# MRCS-Approach-Indicator.net
KiCad netlist of a schematic drawn in EAGLE
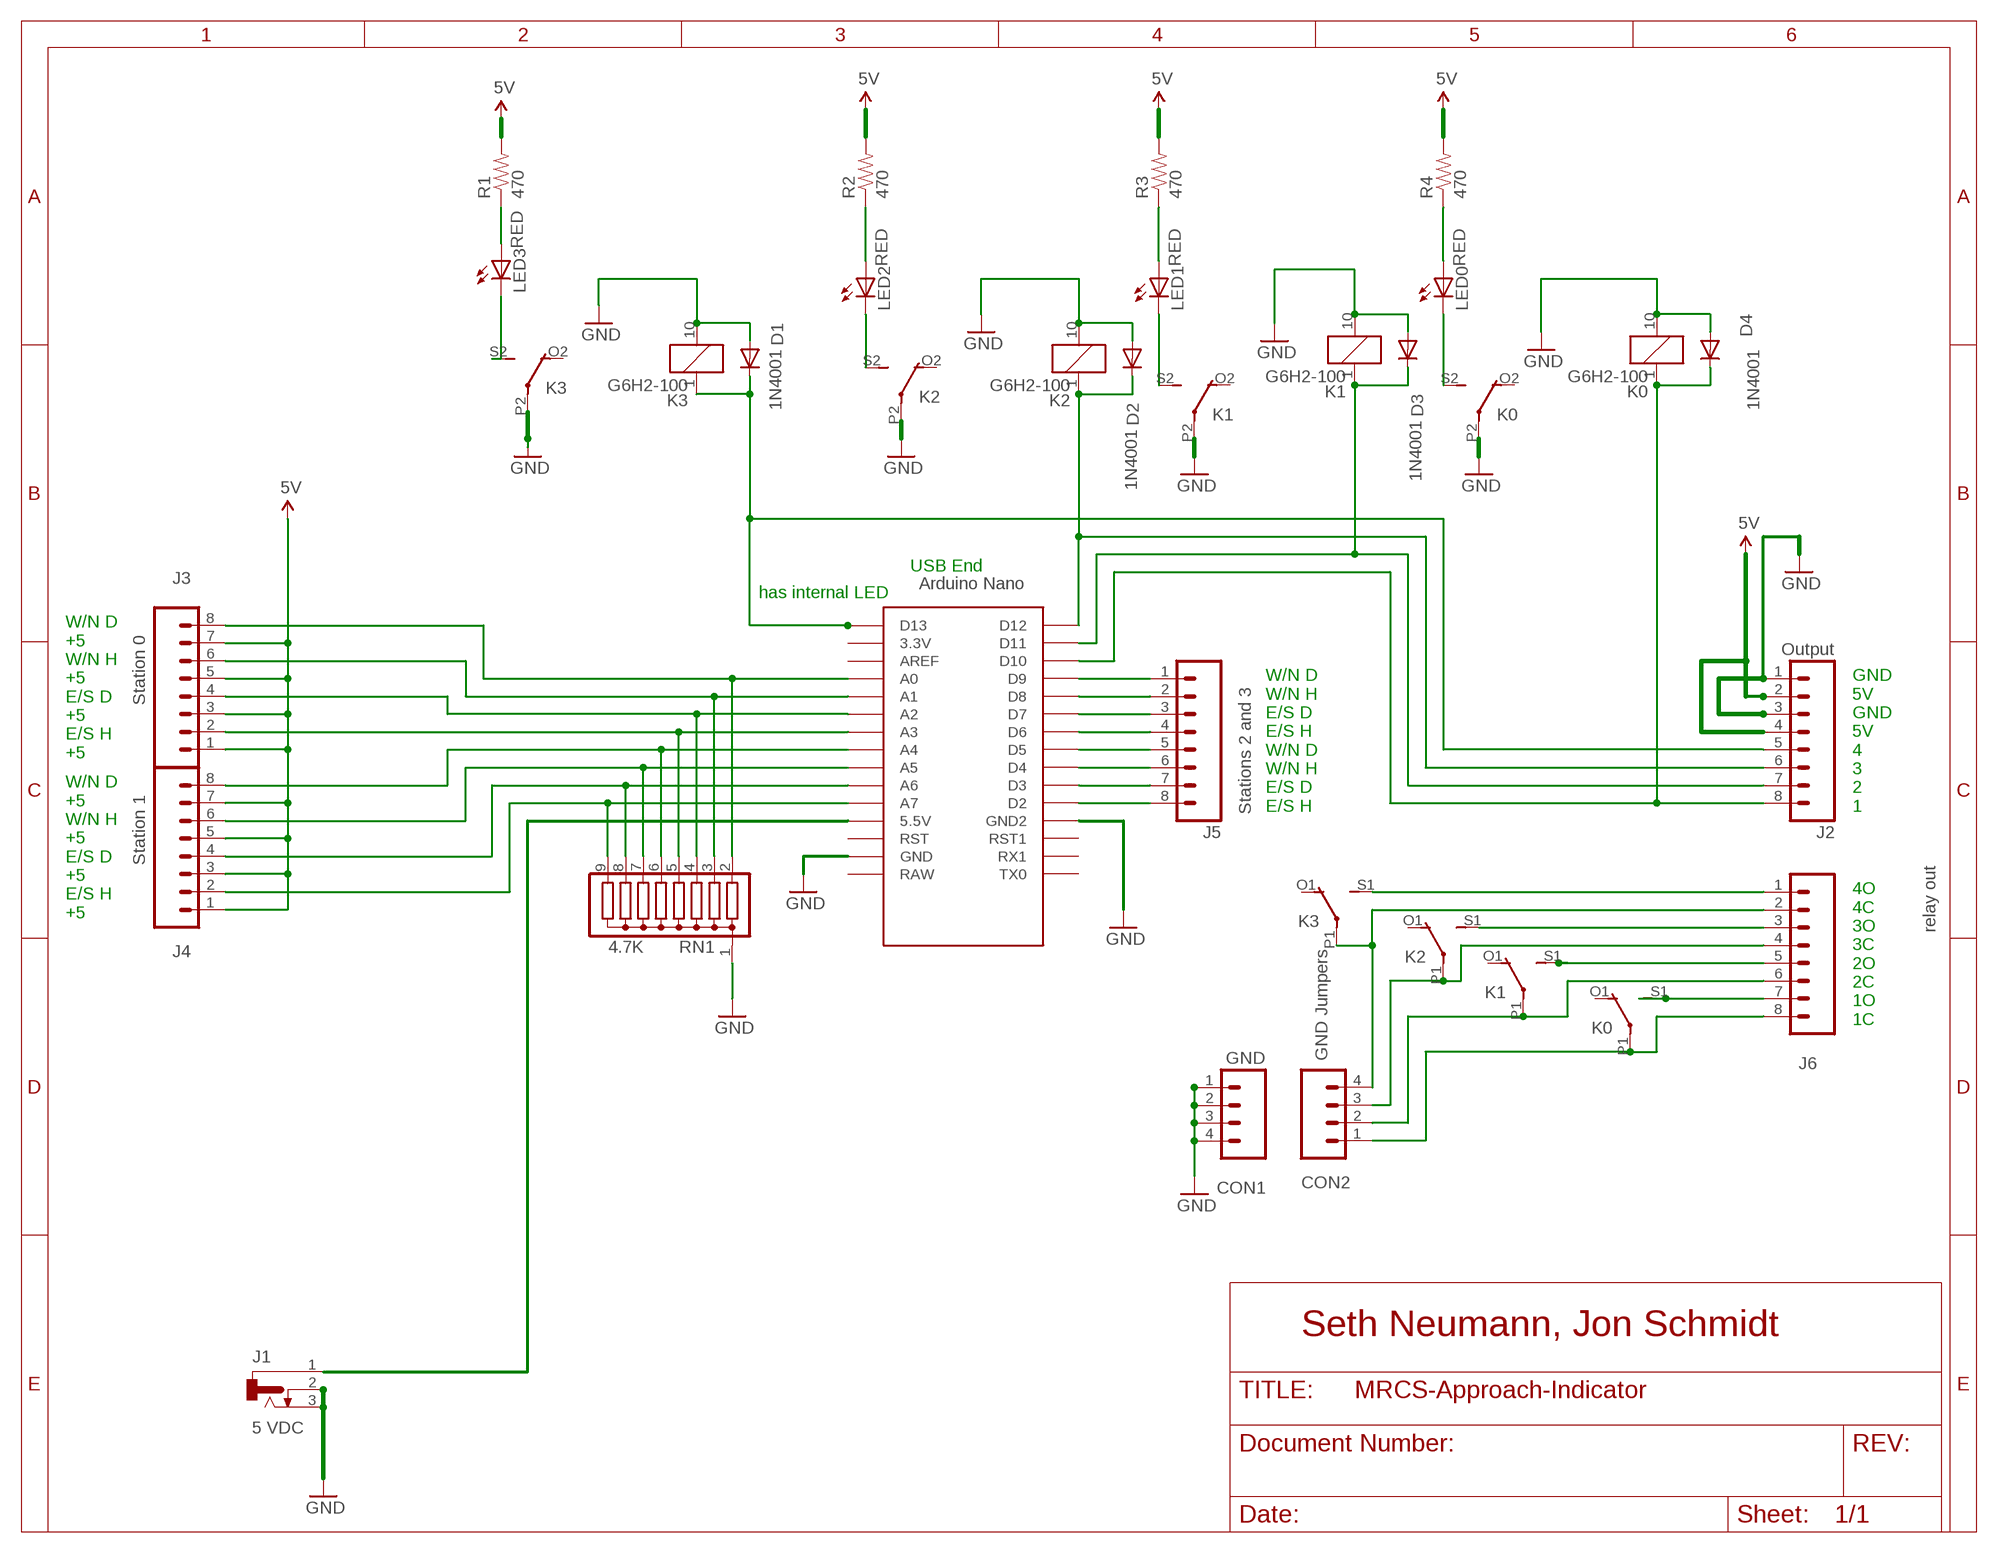
[diagram p0: schematic, sheet 1]

(export (version "E")
  (design (tool "Eeschema 10.0.6"))
  (components
    (comp (ref "CON1")
      (value "GND")
      (footprint "eagle-import:1X04_LOCK")
      (libsource (lib "eagle-import") (part "CONNECTOR-M04LOCK"))
    )
    (comp (ref "CON2")
      (value "GND Jumpers")
      (footprint "eagle-import:1X04_LOCK")
      (libsource (lib "eagle-import") (part "CONNECTOR-M04LOCK"))
    )
    (comp (ref "D1")
      (value "1N4001")
      (footprint "eagle-import:DIODE-1N4001")
      (libsource (lib "eagle-import") (part "DIODEPTH"))
    )
    (comp (ref "D2")
      (value "1N4001")
      (footprint "eagle-import:DIODE-1N4001")
      (libsource (lib "eagle-import") (part "DIODEPTH"))
    )
    (comp (ref "D3")
      (value "1N4001")
      (footprint "eagle-import:DIODE-1N4001")
      (libsource (lib "eagle-import") (part "DIODEPTH"))
    )
    (comp (ref "D4")
      (value "1N4001")
      (footprint "eagle-import:DIODE-1N4001")
      (libsource (lib "eagle-import") (part "DIODEPTH"))
    )
    (comp (ref "J1")
      (value "5 VDC")
      (footprint "eagle-import:DCJ0202")
      (libsource (lib "eagle-import") (part "CONNECTOR-DC-POWER-RA"))
    )
    (comp (ref "J2")
      (value "Output")
      (footprint "eagle-import:1X08_LOCK")
      (libsource (lib "eagle-import") (part "CONNECTOR-M08LOCK"))
    )
    (comp (ref "J3")
      (value "Station 0")
      (footprint "eagle-import:1X08_LOCK")
      (libsource (lib "eagle-import") (part "CONNECTOR-M08LOCK"))
    )
    (comp (ref "J4")
      (value "Station 1")
      (footprint "eagle-import:1X08_LOCK")
      (libsource (lib "eagle-import") (part "CONNECTOR-M08LOCK"))
    )
    (comp (ref "J5")
      (value "Stations 2 and 3")
      (footprint "eagle-import:1X08_LOCK")
      (libsource (lib "eagle-import") (part "CONNECTOR-M08LOCK"))
    )
    (comp (ref "J6")
      (value "relay out")
      (footprint "eagle-import:1X08_LOCK")
      (libsource (lib "eagle-import") (part "CONNECTOR-M08LOCK"))
    )
    (comp (ref "K0")
      (value "G6H2-100")
      (footprint "eagle-import:G6H2-100")
      (libsource (lib "eagle-import") (part "G6H2-100"))
    )
    (comp (ref "K1")
      (value "G6H2-100")
      (footprint "eagle-import:G6H2-100")
      (libsource (lib "eagle-import") (part "G6H2-100"))
    )
    (comp (ref "K2")
      (value "G6H2-100")
      (footprint "eagle-import:G6H2-100")
      (libsource (lib "eagle-import") (part "G6H2-100"))
    )
    (comp (ref "K3")
      (value "G6H2-100")
      (footprint "eagle-import:G6H2-100")
      (libsource (lib "eagle-import") (part "G6H2-100"))
    )
    (comp (ref "LED0")
      (value "RED")
      (footprint "eagle-import:LED3MM")
      (libsource (lib "eagle-import") (part "LEDLED3MM"))
    )
    (comp (ref "LED1")
      (value "RED")
      (footprint "eagle-import:LED3MM")
      (libsource (lib "eagle-import") (part "LEDLED3MM"))
    )
    (comp (ref "LED2")
      (value "RED")
      (footprint "eagle-import:LED3MM")
      (libsource (lib "eagle-import") (part "LEDLED3MM"))
    )
    (comp (ref "LED3")
      (value "RED")
      (footprint "eagle-import:LED3MM")
      (libsource (lib "eagle-import") (part "LEDLED3MM"))
    )
    (comp (ref "NANO")
      (value "NANO")
      (footprint "eagle-import:NANO")
      (libsource (lib "eagle-import") (part "NANO"))
    )
    (comp (ref "R1")
      (value "470")
      (footprint "eagle-import:AXIAL-0.4-RES")
      (libsource (lib "eagle-import") (part "RPTH04"))
    )
    (comp (ref "R2")
      (value "470")
      (footprint "eagle-import:AXIAL-0.4-RES")
      (libsource (lib "eagle-import") (part "RPTH04"))
    )
    (comp (ref "R3")
      (value "470")
      (footprint "eagle-import:AXIAL-0.4-RES")
      (libsource (lib "eagle-import") (part "RPTH04"))
    )
    (comp (ref "R4")
      (value "470")
      (footprint "eagle-import:AXIAL-0.4-RES")
      (libsource (lib "eagle-import") (part "RPTH04"))
    )
    (comp (ref "RN1")
      (value "4.7K")
      (footprint "eagle-import:SIL9")
      (libsource (lib "eagle-import") (part "G08R"))
    )
  )
  (nets
    (net (code "1") (name "5V") (class "Default")
      (node (ref "J1") (pin "1") (pinfunction "1_1") (pintype "passive"))
      (node (ref "J2") (pin "2") (pinfunction "2_2") (pintype "passive"))
      (node (ref "J2") (pin "4") (pinfunction "4_4") (pintype "passive"))
      (node (ref "J3") (pin "1") (pinfunction "1_1") (pintype "passive"))
      (node (ref "J3") (pin "3") (pinfunction "3_3") (pintype "passive"))
      (node (ref "J3") (pin "5") (pinfunction "5_5") (pintype "passive"))
      (node (ref "J3") (pin "7") (pinfunction "7_7") (pintype "passive"))
      (node (ref "J4") (pin "1") (pinfunction "1_1") (pintype "passive"))
      (node (ref "J4") (pin "3") (pinfunction "3_3") (pintype "passive"))
      (node (ref "J4") (pin "5") (pinfunction "5_5") (pintype "passive"))
      (node (ref "J4") (pin "7") (pinfunction "7_7") (pintype "passive"))
      (node (ref "NANO") (pin "5V") (pinfunction "5.5V_5V") (pintype "bidirectional"))
      (node (ref "R1") (pin "P$2") (pinfunction "2_P$2") (pintype "passive"))
      (node (ref "R2") (pin "P$2") (pinfunction "2_P$2") (pintype "passive"))
      (node (ref "R3") (pin "P$2") (pinfunction "2_P$2") (pintype "passive"))
      (node (ref "R4") (pin "P$2") (pinfunction "2_P$2") (pintype "passive"))
    )
    (net (code "2") (name "GND") (class "Default")
      (node (ref "CON1") (pin "1") (pinfunction "1_1") (pintype "passive"))
      (node (ref "CON1") (pin "2") (pinfunction "2_2") (pintype "passive"))
      (node (ref "CON1") (pin "3") (pinfunction "3_3") (pintype "passive"))
      (node (ref "CON1") (pin "4") (pinfunction "4_4") (pintype "passive"))
      (node (ref "D1") (pin "A") (pinfunction "A_A") (pintype "passive"))
      (node (ref "D2") (pin "A") (pinfunction "A_A") (pintype "passive"))
      (node (ref "D3") (pin "A") (pinfunction "A_A") (pintype "passive"))
      (node (ref "D4") (pin "A") (pinfunction "A_A") (pintype "passive"))
      (node (ref "J1") (pin "2") (pinfunction "2_2") (pintype "passive"))
      (node (ref "J1") (pin "3") (pinfunction "3_3") (pintype "passive"))
      (node (ref "J2") (pin "1") (pinfunction "1_1") (pintype "passive"))
      (node (ref "J2") (pin "3") (pinfunction "3_3") (pintype "passive"))
      (node (ref "K0") (pin "10") (pinfunction "2_10") (pintype "passive"))
      (node (ref "K0") (pin "P2") (pinfunction "P_P2") (pintype "passive"))
      (node (ref "K1") (pin "10") (pinfunction "2_10") (pintype "passive"))
      (node (ref "K1") (pin "P2") (pinfunction "P_P2") (pintype "passive"))
      (node (ref "K2") (pin "10") (pinfunction "2_10") (pintype "passive"))
      (node (ref "K2") (pin "P2") (pinfunction "P_P2") (pintype "passive"))
      (node (ref "K3") (pin "10") (pinfunction "2_10") (pintype "passive"))
      (node (ref "K3") (pin "P2") (pinfunction "P_P2") (pintype "passive"))
      (node (ref "NANO") (pin "GND") (pinfunction "GND_GND") (pintype "bidirectional"))
      (node (ref "NANO") (pin "GND1") (pinfunction "GND2_GND1") (pintype "bidirectional"))
      (node (ref "RN1") (pin "1") (pinfunction "1_1") (pintype "passive"))
    )
    (net (code "3") (name "Net-(D1-PadC)") (class "Default")
      (node (ref "D1") (pin "C") (pinfunction "C_C") (pintype "passive"))
      (node (ref "J2") (pin "5") (pinfunction "5_5") (pintype "passive"))
      (node (ref "K3") (pin "1") (pinfunction "1_1") (pintype "passive"))
      (node (ref "NANO") (pin "D13") (pinfunction "D13_D13") (pintype "bidirectional"))
    )
    (net (code "4") (name "Net-(D2-PadC)") (class "Default")
      (node (ref "D2") (pin "C") (pinfunction "C_C") (pintype "passive"))
      (node (ref "J2") (pin "6") (pinfunction "6_6") (pintype "passive"))
      (node (ref "K2") (pin "1") (pinfunction "1_1") (pintype "passive"))
      (node (ref "NANO") (pin "D12") (pinfunction "D12_D12") (pintype "bidirectional"))
    )
    (net (code "5") (name "Net-(D3-PadC)") (class "Default")
      (node (ref "D3") (pin "C") (pinfunction "C_C") (pintype "passive"))
      (node (ref "J2") (pin "7") (pinfunction "7_7") (pintype "passive"))
      (node (ref "K1") (pin "1") (pinfunction "1_1") (pintype "passive"))
      (node (ref "NANO") (pin "D11") (pinfunction "D11_D11") (pintype "bidirectional"))
    )
    (net (code "6") (name "Net-(D4-PadC)") (class "Default")
      (node (ref "D4") (pin "C") (pinfunction "C_C") (pintype "passive"))
      (node (ref "J2") (pin "8") (pinfunction "8_8") (pintype "passive"))
      (node (ref "K0") (pin "1") (pinfunction "1_1") (pintype "passive"))
      (node (ref "NANO") (pin "D10") (pinfunction "D10_D10") (pintype "bidirectional"))
    )
    (net (code "7") (name "Net-(J3-Pad2)") (class "Default")
      (node (ref "J3") (pin "2") (pinfunction "2_2") (pintype "passive"))
      (node (ref "NANO") (pin "A3") (pinfunction "A3_A3") (pintype "bidirectional"))
      (node (ref "RN1") (pin "5") (pinfunction "5_5") (pintype "passive"))
    )
    (net (code "8") (name "Net-(J3-Pad4)") (class "Default")
      (node (ref "J3") (pin "4") (pinfunction "4_4") (pintype "passive"))
      (node (ref "NANO") (pin "A2") (pinfunction "A2_A2") (pintype "bidirectional"))
      (node (ref "RN1") (pin "4") (pinfunction "4_4") (pintype "passive"))
    )
    (net (code "9") (name "Net-(J3-Pad6)") (class "Default")
      (node (ref "J3") (pin "6") (pinfunction "6_6") (pintype "passive"))
      (node (ref "NANO") (pin "A1") (pinfunction "A1_A1") (pintype "bidirectional"))
      (node (ref "RN1") (pin "3") (pinfunction "3_3") (pintype "passive"))
    )
    (net (code "10") (name "Net-(J3-Pad8)") (class "Default")
      (node (ref "J3") (pin "8") (pinfunction "8_8") (pintype "passive"))
      (node (ref "NANO") (pin "A0") (pinfunction "A0_A0") (pintype "bidirectional"))
      (node (ref "RN1") (pin "2") (pinfunction "2_2") (pintype "passive"))
    )
    (net (code "11") (name "Net-(J4-Pad2)") (class "Default")
      (node (ref "J4") (pin "2") (pinfunction "2_2") (pintype "passive"))
      (node (ref "NANO") (pin "A7") (pinfunction "A7_A7") (pintype "bidirectional"))
      (node (ref "RN1") (pin "9") (pinfunction "9_9") (pintype "passive"))
    )
    (net (code "12") (name "Net-(J4-Pad4)") (class "Default")
      (node (ref "J4") (pin "4") (pinfunction "4_4") (pintype "passive"))
      (node (ref "NANO") (pin "A6") (pinfunction "A6_A6") (pintype "bidirectional"))
      (node (ref "RN1") (pin "8") (pinfunction "8_8") (pintype "passive"))
    )
    (net (code "13") (name "Net-(J4-Pad6)") (class "Default")
      (node (ref "J4") (pin "6") (pinfunction "6_6") (pintype "passive"))
      (node (ref "NANO") (pin "A5") (pinfunction "A5_A5") (pintype "bidirectional"))
      (node (ref "RN1") (pin "7") (pinfunction "7_7") (pintype "passive"))
    )
    (net (code "14") (name "Net-(J4-Pad8)") (class "Default")
      (node (ref "J4") (pin "8") (pinfunction "8_8") (pintype "passive"))
      (node (ref "NANO") (pin "A4") (pinfunction "A4_A4") (pintype "bidirectional"))
      (node (ref "RN1") (pin "6") (pinfunction "6_6") (pintype "passive"))
    )
    (net (code "15") (name "Net-(J5-Pad1)") (class "Default")
      (node (ref "J5") (pin "1") (pinfunction "1_1") (pintype "passive"))
      (node (ref "NANO") (pin "D9") (pinfunction "D9_D9") (pintype "bidirectional"))
    )
    (net (code "16") (name "Net-(J5-Pad2)") (class "Default")
      (node (ref "J5") (pin "2") (pinfunction "2_2") (pintype "passive"))
      (node (ref "NANO") (pin "D8") (pinfunction "D8_D8") (pintype "bidirectional"))
    )
    (net (code "17") (name "Net-(J5-Pad3)") (class "Default")
      (node (ref "J5") (pin "3") (pinfunction "3_3") (pintype "passive"))
      (node (ref "NANO") (pin "D7") (pinfunction "D7_D7") (pintype "bidirectional"))
    )
    (net (code "18") (name "Net-(J5-Pad4)") (class "Default")
      (node (ref "J5") (pin "4") (pinfunction "4_4") (pintype "passive"))
      (node (ref "NANO") (pin "D6") (pinfunction "D6_D6") (pintype "bidirectional"))
    )
    (net (code "19") (name "Net-(J5-Pad5)") (class "Default")
      (node (ref "J5") (pin "5") (pinfunction "5_5") (pintype "passive"))
      (node (ref "NANO") (pin "D5") (pinfunction "D5_D5") (pintype "bidirectional"))
    )
    (net (code "20") (name "Net-(J5-Pad6)") (class "Default")
      (node (ref "J5") (pin "6") (pinfunction "6_6") (pintype "passive"))
      (node (ref "NANO") (pin "D4") (pinfunction "D4_D4") (pintype "bidirectional"))
    )
    (net (code "21") (name "Net-(J5-Pad7)") (class "Default")
      (node (ref "J5") (pin "7") (pinfunction "7_7") (pintype "passive"))
      (node (ref "NANO") (pin "D3") (pinfunction "D3_D3") (pintype "bidirectional"))
    )
    (net (code "22") (name "Net-(J5-Pad8)") (class "Default")
      (node (ref "J5") (pin "8") (pinfunction "8_8") (pintype "passive"))
      (node (ref "NANO") (pin "D2") (pinfunction "D2_D2") (pintype "bidirectional"))
    )
    (net (code "23") (name "Net-(K0B-P)") (class "Default")
      (node (ref "CON2") (pin "1") (pinfunction "1_1") (pintype "passive"))
      (node (ref "J6") (pin "8") (pinfunction "8_8") (pintype "passive"))
      (node (ref "K0") (pin "P1") (pinfunction "P_P1") (pintype "passive"))
    )
    (net (code "24") (name "Net-(K0B-S)") (class "Default")
      (node (ref "J6") (pin "7") (pinfunction "7_7") (pintype "passive"))
      (node (ref "K0") (pin "S1") (pinfunction "S_S1") (pintype "passive"))
    )
    (net (code "25") (name "Net-(K0C-S)") (class "Default")
      (node (ref "K0") (pin "S2") (pinfunction "S_S2") (pintype "passive"))
      (node (ref "LED0") (pin "K") (pinfunction "C_K") (pintype "passive"))
    )
    (net (code "26") (name "Net-(K1B-P)") (class "Default")
      (node (ref "CON2") (pin "2") (pinfunction "2_2") (pintype "passive"))
      (node (ref "J6") (pin "6") (pinfunction "6_6") (pintype "passive"))
      (node (ref "K1") (pin "P1") (pinfunction "P_P1") (pintype "passive"))
    )
    (net (code "27") (name "Net-(K1B-S)") (class "Default")
      (node (ref "J6") (pin "5") (pinfunction "5_5") (pintype "passive"))
      (node (ref "K1") (pin "S1") (pinfunction "S_S1") (pintype "passive"))
    )
    (net (code "28") (name "Net-(K1C-S)") (class "Default")
      (node (ref "K1") (pin "S2") (pinfunction "S_S2") (pintype "passive"))
      (node (ref "LED1") (pin "K") (pinfunction "C_K") (pintype "passive"))
    )
    (net (code "29") (name "Net-(K2B-P)") (class "Default")
      (node (ref "CON2") (pin "3") (pinfunction "3_3") (pintype "passive"))
      (node (ref "J6") (pin "4") (pinfunction "4_4") (pintype "passive"))
      (node (ref "K2") (pin "P1") (pinfunction "P_P1") (pintype "passive"))
    )
    (net (code "30") (name "Net-(K2B-S)") (class "Default")
      (node (ref "J6") (pin "3") (pinfunction "3_3") (pintype "passive"))
      (node (ref "K2") (pin "S1") (pinfunction "S_S1") (pintype "passive"))
    )
    (net (code "31") (name "Net-(K2C-S)") (class "Default")
      (node (ref "K2") (pin "S2") (pinfunction "S_S2") (pintype "passive"))
      (node (ref "LED2") (pin "K") (pinfunction "C_K") (pintype "passive"))
    )
    (net (code "32") (name "Net-(K3B-P)") (class "Default")
      (node (ref "CON2") (pin "4") (pinfunction "4_4") (pintype "passive"))
      (node (ref "J6") (pin "2") (pinfunction "2_2") (pintype "passive"))
      (node (ref "K3") (pin "P1") (pinfunction "P_P1") (pintype "passive"))
    )
    (net (code "33") (name "Net-(K3B-S)") (class "Default")
      (node (ref "J6") (pin "1") (pinfunction "1_1") (pintype "passive"))
      (node (ref "K3") (pin "S1") (pinfunction "S_S1") (pintype "passive"))
    )
    (net (code "34") (name "Net-(K3C-S)") (class "Default")
      (node (ref "K3") (pin "S2") (pinfunction "S_S2") (pintype "passive"))
      (node (ref "LED3") (pin "K") (pinfunction "C_K") (pintype "passive"))
    )
    (net (code "35") (name "Net-(R1-1)") (class "Default")
      (node (ref "LED3") (pin "A") (pinfunction "A_A") (pintype "passive"))
      (node (ref "R1") (pin "P$1") (pinfunction "1_P$1") (pintype "passive"))
    )
    (net (code "36") (name "Net-(R2-1)") (class "Default")
      (node (ref "LED2") (pin "A") (pinfunction "A_A") (pintype "passive"))
      (node (ref "R2") (pin "P$1") (pinfunction "1_P$1") (pintype "passive"))
    )
    (net (code "37") (name "Net-(R3-1)") (class "Default")
      (node (ref "LED1") (pin "A") (pinfunction "A_A") (pintype "passive"))
      (node (ref "R3") (pin "P$1") (pinfunction "1_P$1") (pintype "passive"))
    )
    (net (code "38") (name "Net-(R4-1)") (class "Default")
      (node (ref "LED0") (pin "A") (pinfunction "A_A") (pintype "passive"))
      (node (ref "R4") (pin "P$1") (pinfunction "1_P$1") (pintype "passive"))
    )
    (net (code "39") (name "unconnected-(K0B-O-PadO1)") (class "Default")
      (node (ref "K0") (pin "O1") (pinfunction "O_O1") (pintype "passive"))
    )
    (net (code "40") (name "unconnected-(K0C-O-PadO2)") (class "Default")
      (node (ref "K0") (pin "O2") (pinfunction "O_O2") (pintype "passive"))
    )
    (net (code "41") (name "unconnected-(K1B-O-PadO1)") (class "Default")
      (node (ref "K1") (pin "O1") (pinfunction "O_O1") (pintype "passive"))
    )
    (net (code "42") (name "unconnected-(K1C-O-PadO2)") (class "Default")
      (node (ref "K1") (pin "O2") (pinfunction "O_O2") (pintype "passive"))
    )
    (net (code "43") (name "unconnected-(K2B-O-PadO1)") (class "Default")
      (node (ref "K2") (pin "O1") (pinfunction "O_O1") (pintype "passive"))
    )
    (net (code "44") (name "unconnected-(K2C-O-PadO2)") (class "Default")
      (node (ref "K2") (pin "O2") (pinfunction "O_O2") (pintype "passive"))
    )
    (net (code "45") (name "unconnected-(K3B-O-PadO1)") (class "Default")
      (node (ref "K3") (pin "O1") (pinfunction "O_O1") (pintype "passive"))
    )
    (net (code "46") (name "unconnected-(K3C-O-PadO2)") (class "Default")
      (node (ref "K3") (pin "O2") (pinfunction "O_O2") (pintype "passive"))
    )
    (net (code "47") (name "unconnected-(NANO-Pad3.3V)") (class "Default")
      (node (ref "NANO") (pin "3.3V") (pinfunction "3.3V_3.3V") (pintype "bidirectional"))
    )
    (net (code "48") (name "unconnected-(NANO-PadAREF)") (class "Default")
      (node (ref "NANO") (pin "AREF") (pinfunction "AREF_AREF") (pintype "bidirectional"))
    )
    (net (code "49") (name "unconnected-(NANO-PadRAW)") (class "Default")
      (node (ref "NANO") (pin "RAW") (pinfunction "RAW_RAW") (pintype "bidirectional"))
    )
    (net (code "50") (name "unconnected-(NANO-PadRST)") (class "Default")
      (node (ref "NANO") (pin "RST") (pinfunction "RST_RST") (pintype "bidirectional"))
    )
    (net (code "51") (name "unconnected-(NANO-PadRST1)") (class "Default")
      (node (ref "NANO") (pin "RST1") (pinfunction "RST1_RST1") (pintype "bidirectional"))
    )
    (net (code "52") (name "unconnected-(NANO-PadRX1)") (class "Default")
      (node (ref "NANO") (pin "RX1") (pinfunction "RX1_RX1") (pintype "bidirectional"))
    )
    (net (code "53") (name "unconnected-(NANO-PadTX0)") (class "Default")
      (node (ref "NANO") (pin "TX0") (pinfunction "TX0_TX0") (pintype "bidirectional"))
    )
  )
)
